# TidePod.net
KiCad netlist of a schematic drawn in EAGLE
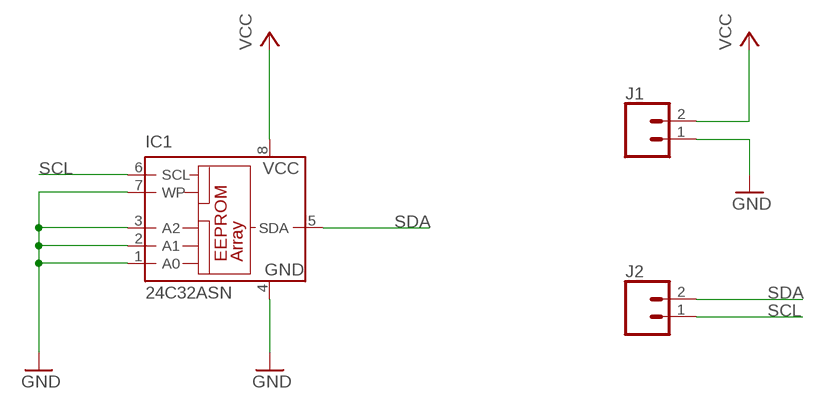
[diagram p0: schematic, sheet 1]

(export (version "E")
  (design (tool "Eeschema 10.0.6"))
  (components
    (comp (ref "IC1")
      (value "24C32ASN")
      (footprint "eagle-import:SO-08")
      (fields (field (name "MPN") "IS24C32A-2GLI"))
      (libsource (lib "eagle-import") (part "24SNC32A"))
    )
    (comp (ref "J1")
      (value "CONN_021X02_NO_SILK")
      (footprint "eagle-import:1X02_NO_SILK")
      (libsource (lib "eagle-import") (part "CONN_021X02_NO_SILK"))
    )
    (comp (ref "J2")
      (value "CONN_021X02_NO_SILK")
      (footprint "eagle-import:1X02_NO_SILK")
      (libsource (lib "eagle-import") (part "CONN_021X02_NO_SILK"))
    )
  )
  (nets
    (net (code "1") (name "/SCL") (class "Default")
      (node (ref "IC1") (pin "6") (pinfunction "SCL_6") (pintype "input"))
      (node (ref "J2") (pin "1") (pinfunction "1_1") (pintype "passive"))
    )
    (net (code "2") (name "/SDA") (class "Default")
      (node (ref "IC1") (pin "5") (pinfunction "SDA_5") (pintype "bidirectional"))
      (node (ref "J2") (pin "2") (pinfunction "2_2") (pintype "passive"))
    )
    (net (code "3") (name "GND") (class "Default")
      (node (ref "IC1") (pin "1") (pinfunction "A0_1") (pintype "input"))
      (node (ref "IC1") (pin "2") (pinfunction "A1_2") (pintype "input"))
      (node (ref "IC1") (pin "3") (pinfunction "A2_3") (pintype "input"))
      (node (ref "IC1") (pin "4") (pinfunction "GND_4") (pintype "power_in"))
      (node (ref "IC1") (pin "7") (pinfunction "WP_7") (pintype "input"))
      (node (ref "J1") (pin "1") (pinfunction "1_1") (pintype "passive"))
    )
    (net (code "4") (name "VCC") (class "Default")
      (node (ref "IC1") (pin "8") (pinfunction "VCC_8") (pintype "power_in"))
      (node (ref "J1") (pin "2") (pinfunction "2_2") (pintype "passive"))
    )
  )
)
